# uSD_CARD.net
KiCad netlist of a schematic drawn in Altium Designer
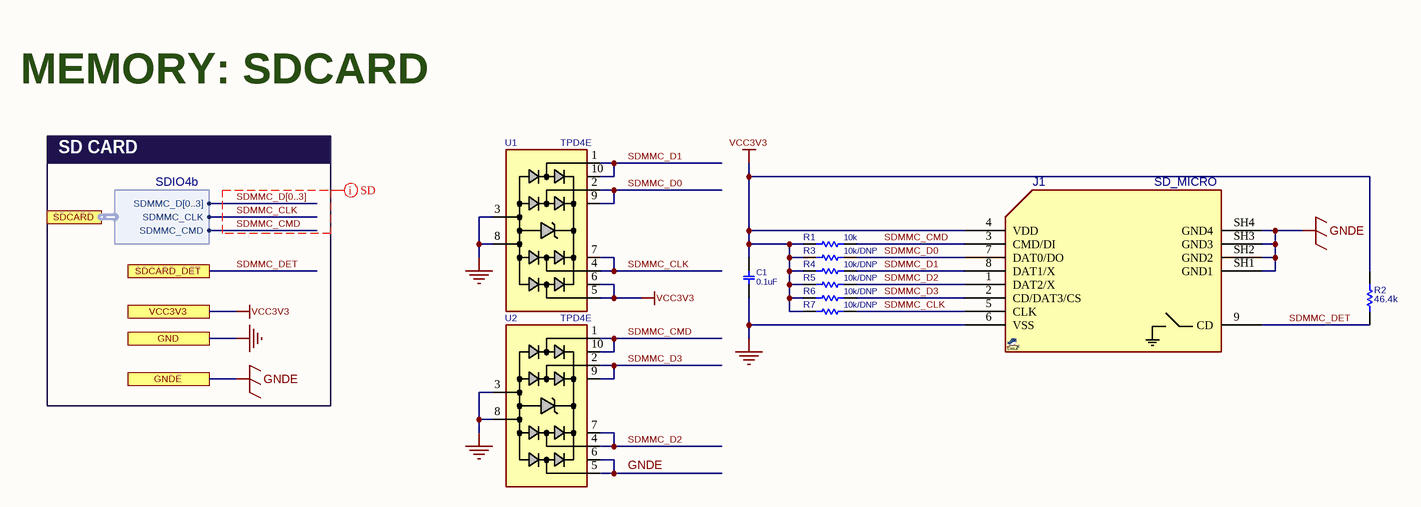
[diagram p0: uSD_CARD.SchDoc]

(export (version "E")
  (design (tool "Eeschema 10.0.6"))
  (components
    (comp (ref "C1")
      (value "0.1uF")
      (footprint "C0603")
      (description "CAP, MLCC")
      (fields (field (name "MANF_P#") "GRM155R61E104") (field (name "MANF") "Murata"))
      (libsource (lib "mlcc_smd_passive") (part "CAP_SMD_MLCC_100n50TDK"))
    )
    (comp (ref "J1")
      (value "SD_MICRO")
      (footprint "SDMICRO_AT")
      (description "SD MICRO exist in Iran, Attend 112J-TDAR-R01")
      (fields (field (name "MANF") "Attend") (field (name "MANF_P#") "112J-TDAR-R01"))
      (libsource (lib "socket_card") (part "SOCKET_SDMICRO_AT"))
    )
    (comp (ref "R1")
      (value "10k")
      (footprint "R0603")
      (description "RESISTOR, SMD")
      (libsource (lib "passive_res_smd") (part "RES_SMD"))
    )
    (comp (ref "R2")
      (value "46.4k")
      (footprint "R0603")
      (description "RESISTOR, SMD")
      (libsource (lib "passive_res_smd") (part "RES_SMD"))
    )
    (comp (ref "R3")
      (value "10k/DNP")
      (footprint "R0603")
      (description "RESISTOR, SMD")
      (libsource (lib "passive_res_smd") (part "RES_SMD"))
    )
    (comp (ref "R4")
      (value "10k/DNP")
      (footprint "R0603")
      (description "RESISTOR, SMD")
      (libsource (lib "passive_res_smd") (part "RES_SMD"))
    )
    (comp (ref "R5")
      (value "10k/DNP")
      (footprint "R0603")
      (description "RESISTOR, SMD")
      (libsource (lib "passive_res_smd") (part "RES_SMD"))
    )
    (comp (ref "R6")
      (value "10k/DNP")
      (footprint "R0603")
      (description "RESISTOR, SMD")
      (libsource (lib "passive_res_smd") (part "RES_SMD"))
    )
    (comp (ref "R7")
      (value "10k/DNP")
      (footprint "R0603")
      (description "RESISTOR, SMD")
      (libsource (lib "passive_res_smd") (part "RES_SMD"))
    )
    (comp (ref "U1")
      (value "TPD4E")
      (footprint "SON50_10_2510")
      (description "TVS, ESD PROTECT, 4CH,")
      (fields (field (name "MANF_P#") "TPD4E05U06DQA") (field (name "MANF") "Texas Instruments"))
      (libsource (lib "protect_tvs_esd_fuse") (part "TVS_X4_TPD4E05U06"))
    )
    (comp (ref "U2")
      (value "TPD4E")
      (footprint "SON50_10_2510")
      (description "TVS, ESD PROTECT, 4CH,")
      (fields (field (name "MANF_P#") "TPD4E05U06DQA") (field (name "MANF") "Texas Instruments"))
      (libsource (lib "protect_tvs_esd_fuse") (part "TVS_X4_TPD4E05U06"))
    )
  )
  (nets
    (net (code "2") (name "/SDMMC_CLK") (class "Default")
      (node (ref "J1") (pin "5") (pinfunction "CLK_5") (pintype "passive"))
      (node (ref "R7") (pin "2") (pinfunction "2_2") (pintype "passive"))
      (node (ref "U1") (pin "4") (pinfunction "4_4") (pintype "passive"))
      (node (ref "U1") (pin "7") (pinfunction "7_7") (pintype "passive"))
    )
    (net (code "3") (name "/SDMMC_CMD") (class "Default")
      (node (ref "J1") (pin "3") (pinfunction "CMD/DI_3") (pintype "passive"))
      (node (ref "R1") (pin "2") (pinfunction "2_2") (pintype "passive"))
      (node (ref "U2") (pin "1") (pinfunction "1_1") (pintype "passive"))
      (node (ref "U2") (pin "10") (pinfunction "10_10") (pintype "passive"))
    )
    (net (code "4") (name "/SDMMC_D0") (class "Default")
      (node (ref "J1") (pin "7") (pinfunction "DAT0/DO_7") (pintype "passive"))
      (node (ref "R3") (pin "2") (pinfunction "2_2") (pintype "passive"))
      (node (ref "U1") (pin "2") (pinfunction "2_2") (pintype "passive"))
      (node (ref "U1") (pin "9") (pinfunction "9_9") (pintype "passive"))
    )
    (net (code "5") (name "/SDMMC_D1") (class "Default")
      (node (ref "J1") (pin "8") (pinfunction "DAT1/X_8") (pintype "passive"))
      (node (ref "R4") (pin "2") (pinfunction "2_2") (pintype "passive"))
      (node (ref "U1") (pin "1") (pinfunction "1_1") (pintype "passive"))
      (node (ref "U1") (pin "10") (pinfunction "10_10") (pintype "passive"))
    )
    (net (code "6") (name "/SDMMC_D2") (class "Default")
      (node (ref "J1") (pin "1") (pinfunction "DAT2/X_1") (pintype "passive"))
      (node (ref "R5") (pin "2") (pinfunction "2_2") (pintype "passive"))
      (node (ref "U2") (pin "4") (pinfunction "4_4") (pintype "passive"))
      (node (ref "U2") (pin "7") (pinfunction "7_7") (pintype "passive"))
    )
    (net (code "7") (name "/SDMMC_D3") (class "Default")
      (node (ref "J1") (pin "2") (pinfunction "CD/DAT3/CS_2") (pintype "passive"))
      (node (ref "R6") (pin "2") (pinfunction "2_2") (pintype "passive"))
      (node (ref "U2") (pin "2") (pinfunction "2_2") (pintype "passive"))
      (node (ref "U2") (pin "9") (pinfunction "9_9") (pintype "passive"))
    )
    (net (code "8") (name "/SDMMC_DET") (class "Default")
      (node (ref "J1") (pin "9") (pinfunction "CD_9") (pintype "passive"))
      (node (ref "R2") (pin "1") (pinfunction "1_1") (pintype "passive"))
    )
    (net (code "11") (name "GND") (class "Default")
      (node (ref "C1") (pin "2") (pinfunction "2_2") (pintype "passive"))
      (node (ref "J1") (pin "6") (pinfunction "VSS_6") (pintype "passive"))
      (node (ref "U1") (pin "3") (pinfunction "3_3") (pintype "passive"))
      (node (ref "U1") (pin "8") (pinfunction "8_8") (pintype "passive"))
      (node (ref "U2") (pin "3") (pinfunction "3_3") (pintype "passive"))
      (node (ref "U2") (pin "8") (pinfunction "8_8") (pintype "passive"))
    )
    (net (code "12") (name "GNDE") (class "Default")
      (node (ref "J1") (pin "SH1") (pinfunction "GND1_SH1") (pintype "passive"))
      (node (ref "J1") (pin "SH2") (pinfunction "GND2_SH2") (pintype "passive"))
      (node (ref "J1") (pin "SH3") (pinfunction "GND3_SH3") (pintype "passive"))
      (node (ref "J1") (pin "SH4") (pinfunction "GND4_SH4") (pintype "passive"))
      (node (ref "U2") (pin "5") (pinfunction "5_5") (pintype "passive"))
      (node (ref "U2") (pin "6") (pinfunction "6_6") (pintype "passive"))
    )
    (net (code "13") (name "VCC3V3") (class "Default")
      (node (ref "C1") (pin "1") (pinfunction "1_1") (pintype "passive"))
      (node (ref "J1") (pin "4") (pinfunction "VDD_4") (pintype "passive"))
      (node (ref "R1") (pin "1") (pinfunction "1_1") (pintype "passive"))
      (node (ref "R2") (pin "2") (pinfunction "2_2") (pintype "passive"))
      (node (ref "R3") (pin "1") (pinfunction "1_1") (pintype "passive"))
      (node (ref "R4") (pin "1") (pinfunction "1_1") (pintype "passive"))
      (node (ref "R5") (pin "1") (pinfunction "1_1") (pintype "passive"))
      (node (ref "R6") (pin "1") (pinfunction "1_1") (pintype "passive"))
      (node (ref "R7") (pin "1") (pinfunction "1_1") (pintype "passive"))
      (node (ref "U1") (pin "5") (pinfunction "5_5") (pintype "passive"))
      (node (ref "U1") (pin "6") (pinfunction "6_6") (pintype "passive"))
    )
  )
)
